# 2N3904_SWITCH_LVTTL.net
KiCad netlist of a schematic drawn in Altium Designer
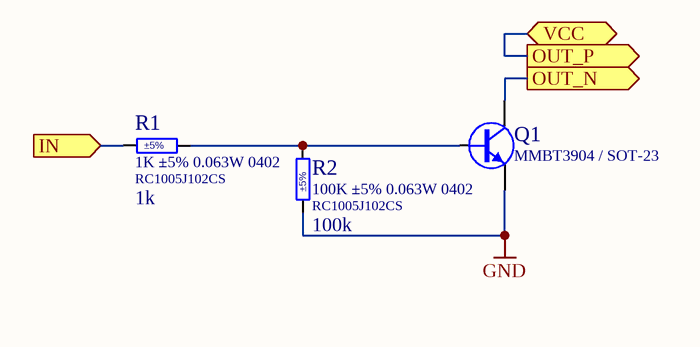
[diagram p0: 2N3904_SWITCH_LVTTL.SchDoc]

(export (version "E")
  (design (tool "Eeschema 10.0.6"))
  (components
    (comp (ref "Q1")
      (value "MMBT3904 /")
      (footprint "SOT_SC:SOT-23")
      (description "General Purpose Transistor")
      (libsource (lib "TRANSISTORS") (part "MMBT3904"))
    )
    (comp (ref "R1")
      (value "1K ±5% 0.063W")
      (footprint "RES_SMD:0402")
      (description "Thin Film Chip Resistor")
      (fields
        (field (name "POWER") "0.063W")
        (field (name "TOLERANCE") "±5%")
        (field (name "NAME") "RC1005J102CS")
        (field (name "ALTIUM_VALUE") "1k")
      )
      (libsource (lib "PASSIVE") (part "Resistor"))
    )
    (comp (ref "R2")
      (value "100K ±5% 0.063W")
      (footprint "RES_SMD:0402")
      (description "Thin Film Chip Resistor")
      (fields
        (field (name "POWER") "0.063W")
        (field (name "TOLERANCE") "±5%")
        (field (name "NAME") "RC1005J102CS")
        (field (name "ALTIUM_VALUE") "100k")
      )
      (libsource (lib "PASSIVE") (part "Resistor"))
    )
  )
  (nets
    (net (code "1") (name "/IN") (class "Default")
      (node (ref "R1") (pin "1") (pinfunction "1_1") (pintype "passive"))
    )
    (net (code "2") (name "/OUT_N") (class "Default")
      (node (ref "Q1") (pin "3") (pinfunction "C_3") (pintype "passive"))
    )
    (net (code "4") (name "GND") (class "Default")
      (node (ref "Q1") (pin "2") (pinfunction "E_2") (pintype "passive"))
      (node (ref "R2") (pin "1") (pinfunction "1_1") (pintype "passive"))
    )
    (net (code "5") (name "Net-(Q1-B)") (class "Default")
      (node (ref "Q1") (pin "1") (pinfunction "B_1") (pintype "passive"))
      (node (ref "R1") (pin "2") (pinfunction "2_2") (pintype "passive"))
      (node (ref "R2") (pin "2") (pinfunction "2_2") (pintype "passive"))
    )
  )
)
